# USB_OTG_AND_HOST.net
KiCad netlist of a schematic drawn in Altium Designer
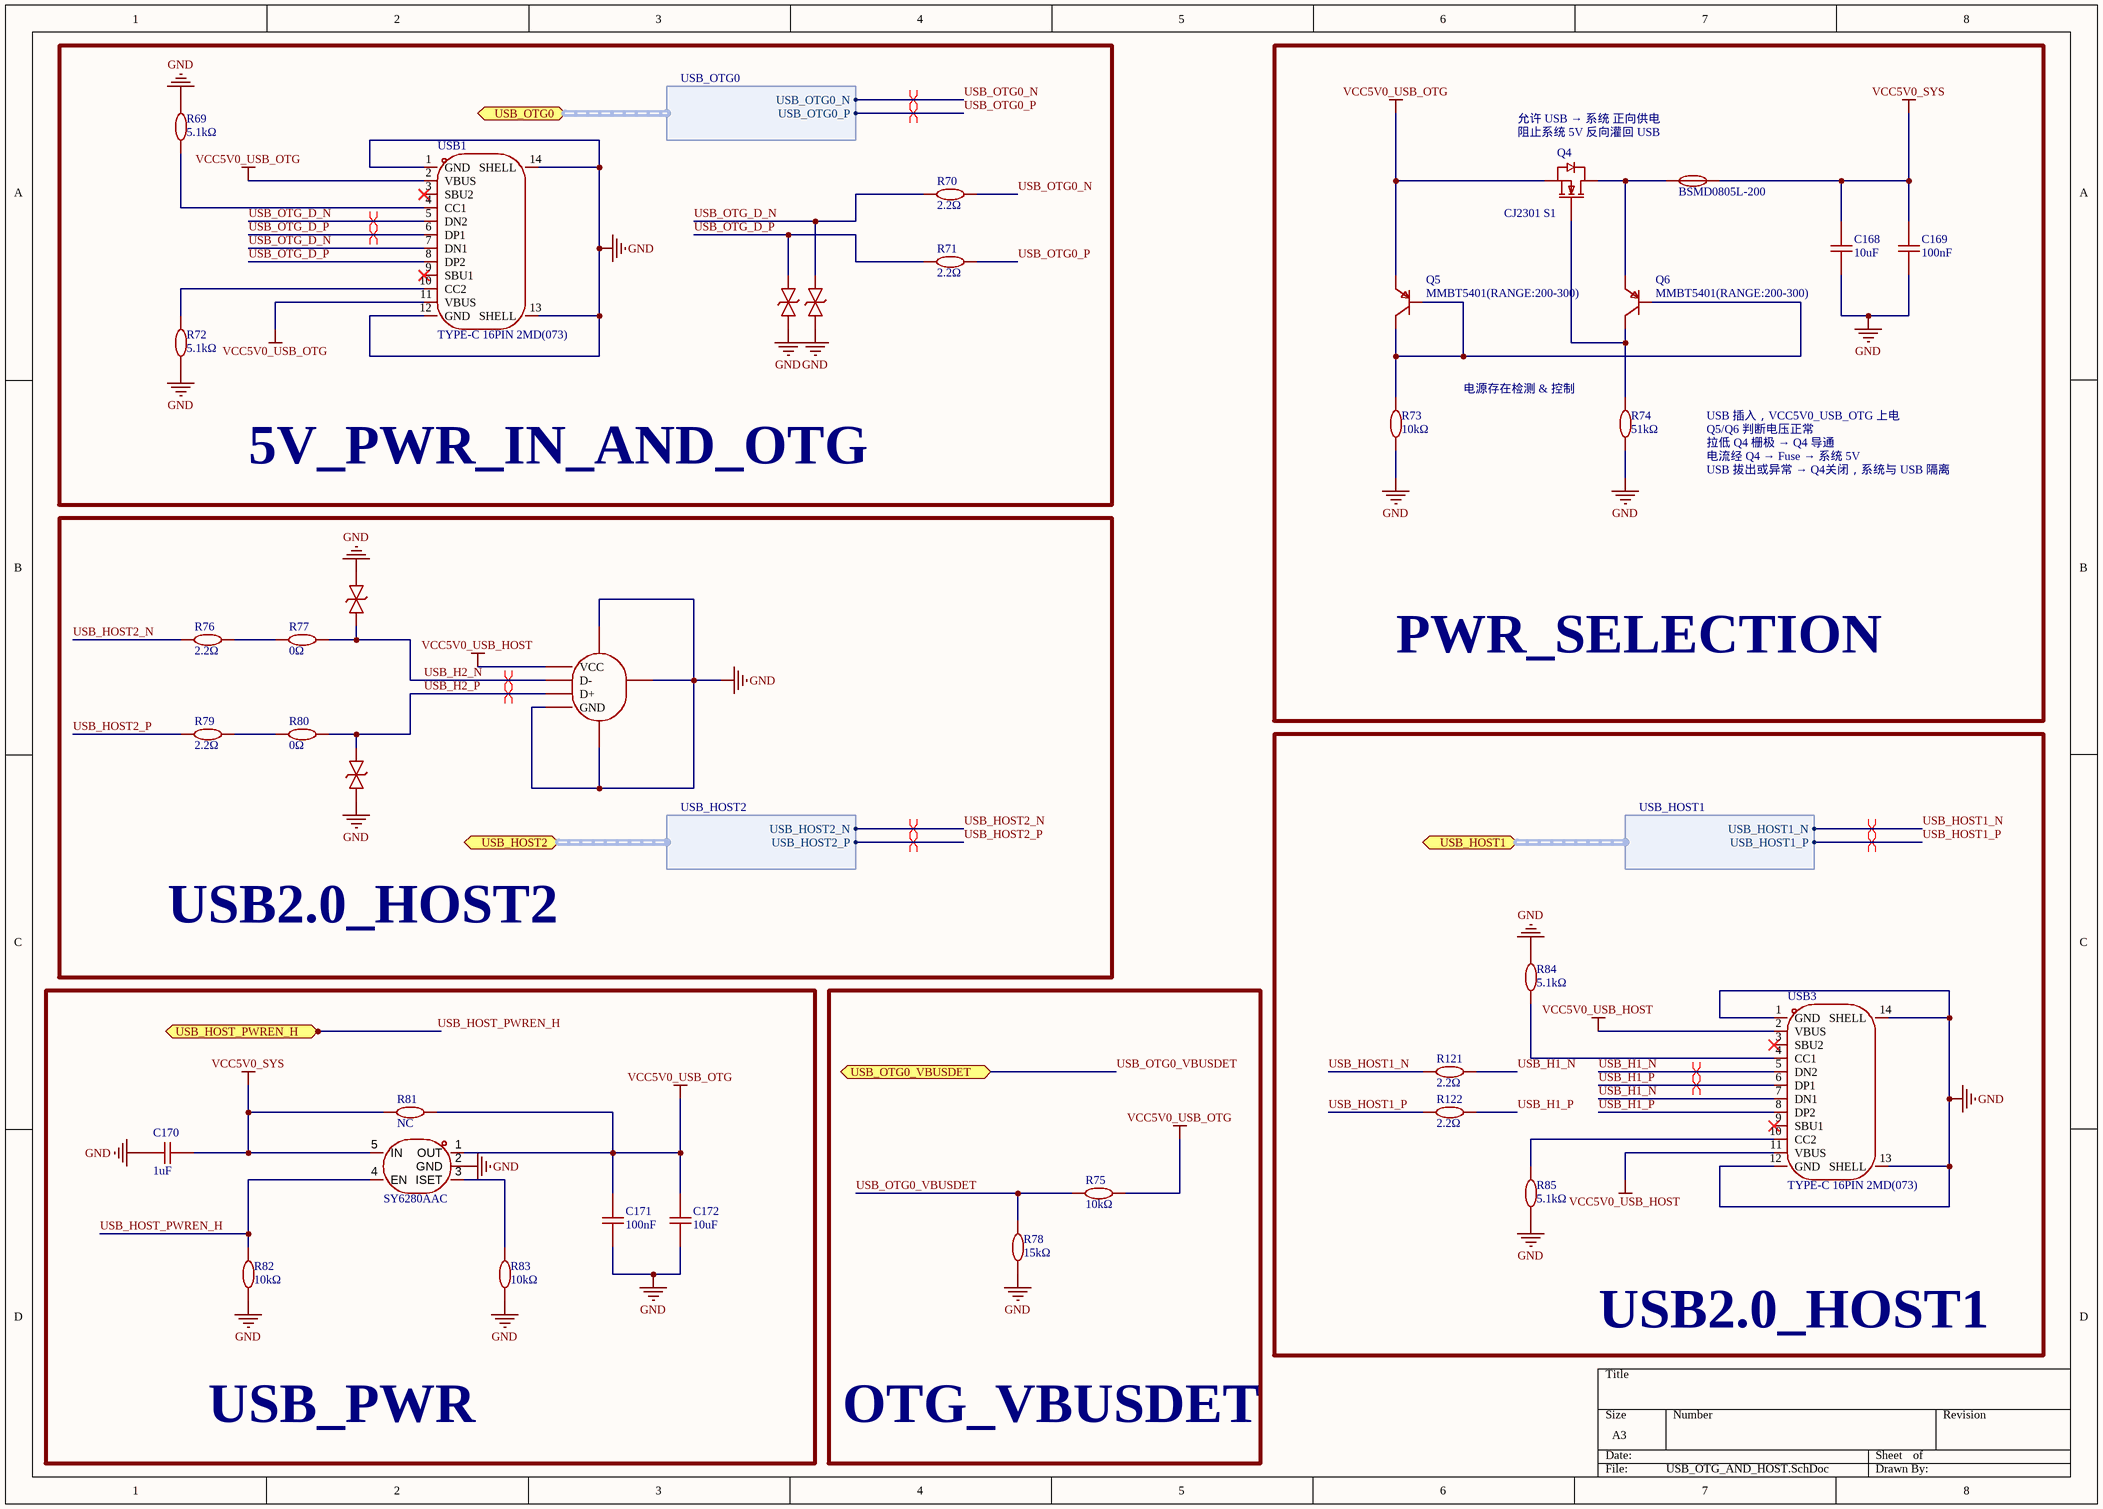
[diagram p0: USB_OTG_AND_HOST.SchDoc]

(export (version "E")
  (design (tool "Eeschema 10.0.6"))
  (components
    (comp (ref "C168")
      (value "10uF")
      (footprint "C0603")
      (description "10V 10uF X5R ±10% 0603 Ceramic Capacitors ROHS")
      (libsource (lib "RLC") (part "10uF"))
    )
    (comp (ref "C169")
      (value "100nF")
      (footprint "C0402")
      (description "50V 100nF X7R ±10% 0402 Ceramic Capacitors ROHS")
      (libsource (lib "RLC") (part "100nF"))
    )
    (comp (ref "C170")
      (value "1uF")
      (footprint "C0402")
      (description "50V 1uF X5R ±10% 0402 Ceramic Capacitors ROHS")
      (libsource (lib "RLC") (part "1uF"))
    )
    (comp (ref "C171")
      (value "100nF")
      (footprint "C0402")
      (description "50V 100nF X7R ±10% 0402 Ceramic Capacitors ROHS")
      (libsource (lib "RLC") (part "100nF"))
    )
    (comp (ref "C172")
      (value "10uF")
      (footprint "C0603")
      (description "10V 10uF X5R ±10% 0603 Ceramic Capacitors ROHS")
      (libsource (lib "RLC") (part "10uF"))
    )
    (comp (ref "F1")
      (value "BSMD0805L-200")
      (footprint "F0805")
      (description "6V 2A 0805自恢复")
      (libsource (lib "LED") (part "BSMD0805L-200"))
    )
    (comp (ref "Q4")
      (value "CJ2301 S1")
      (footprint "SOT-23_L2.9-W1.3-P1.90-LS2.4-BR")
      (description "1个P沟道 耐压:20V 电流:2.3A ,-20V,-2.3A,112mΩ@-4.5V")
      (libsource (lib "Transistor") (part "CJ2301 S1"))
    )
    (comp (ref "Q5")
      (value "MMBT5401(RANGE:200-300)")
      (footprint "SOT-23_L2.9-W1.3-P1.90-LS2.4-BR")
      (description "PNP hfe=200~300 PNP 电流:0.6A 电压:150V")
      (libsource (lib "Transistor") (part "MMBT5401(RANGE{colon}200-300)"))
    )
    (comp (ref "Q6")
      (value "MMBT5401(RANGE:200-300)")
      (footprint "SOT-23_L2.9-W1.3-P1.90-LS2.4-BR")
      (description "PNP hfe=200~300 PNP 电流:0.6A 电压:150V")
      (libsource (lib "Transistor") (part "MMBT5401(RANGE{colon}200-300)"))
    )
    (comp (ref "R69")
      (value "5.1kΩ")
      (footprint "R0402")
      (description "5.1kΩ 62.5mW 50V ±100ppm/℃ Thick Film Resistor ±1% 0402 Chip Resistor - Surface Mount ROHS")
      (libsource (lib "RLC") (part "5.1kΩ"))
    )
    (comp (ref "R70")
      (value "2.2Ω")
      (footprint "R0402")
      (description "小尺寸、重量轻。降低组装成本,与贴片机匹配。适用于波峰焊和回流焊")
      (libsource (lib "RLC") (part "2.2Ω"))
    )
    (comp (ref "R71")
      (value "2.2Ω")
      (footprint "R0402")
      (description "小尺寸、重量轻。降低组装成本,与贴片机匹配。适用于波峰焊和回流焊")
      (libsource (lib "RLC") (part "2.2Ω"))
    )
    (comp (ref "R72")
      (value "5.1kΩ")
      (footprint "R0402")
      (description "5.1kΩ 62.5mW 50V ±100ppm/℃ Thick Film Resistor ±1% 0402 Chip Resistor - Surface Mount ROHS")
      (libsource (lib "RLC") (part "5.1kΩ"))
    )
    (comp (ref "R73")
      (value "10kΩ")
      (footprint "R0402")
      (description "62.5mW 10kΩ 50V ±100ppm/℃ Thick Film Resistor ±1% 0402 Chip Resistor - Surface Mount ROHS")
      (libsource (lib "RLC") (part "10kΩ"))
    )
    (comp (ref "R74")
      (value "51kΩ")
      (footprint "R0402")
      (description "51kΩ 62.5mW 50V ±100ppm/℃ Thick Film Resistor ±1% 0402 Chip Resistor - Surface Mount ROHS")
      (libsource (lib "RLC") (part "51kΩ"))
    )
    (comp (ref "R75")
      (value "10kΩ")
      (footprint "R0402")
      (description "62.5mW 10kΩ 50V ±100ppm/℃ Thick Film Resistor ±1% 0402 Chip Resistor - Surface Mount ROHS")
      (libsource (lib "RLC") (part "10kΩ"))
    )
    (comp (ref "R76")
      (value "2.2Ω")
      (footprint "R0402")
      (description "小尺寸、重量轻。降低组装成本,与贴片机匹配。适用于波峰焊和回流焊")
      (libsource (lib "RLC") (part "2.2Ω"))
    )
    (comp (ref "R77")
      (value "0Ω")
      (footprint "R0402")
      (description "0Ω 62.5mW 50V Thick Film Resistor ±1% 0402 Chip Resistor - Surface Mount ROHS")
      (libsource (lib "RLC") (part "0Ω"))
    )
    (comp (ref "R78")
      (value "15kΩ")
      (footprint "R0402")
      (description "62.5mW 15kΩ 50V ±100ppm/℃ Thick Film Resistor ±1% 0402 Chip Resistor - Surface Mount ROHS")
      (libsource (lib "RLC") (part "15kΩ"))
    )
    (comp (ref "R79")
      (value "2.2Ω")
      (footprint "R0402")
      (description "小尺寸、重量轻。降低组装成本,与贴片机匹配。适用于波峰焊和回流焊")
      (libsource (lib "RLC") (part "2.2Ω"))
    )
    (comp (ref "R80")
      (value "0Ω")
      (footprint "R0402")
      (description "0Ω 62.5mW 50V Thick Film Resistor ±1% 0402 Chip Resistor - Surface Mount ROHS")
      (libsource (lib "RLC") (part "0Ω"))
    )
    (comp (ref "R81")
      (value "NC")
      (footprint "R0402")
      (description "10Ω 62.5mW 50V ±200ppm/℃ Thick Film Resistor ±1% 0402 Chip Resistor - Surface Mount ROHS")
      (libsource (lib "RLC") (part "10Ω"))
    )
    (comp (ref "R82")
      (value "10kΩ")
      (footprint "R0402")
      (description "62.5mW 10kΩ 50V ±100ppm/℃ Thick Film Resistor ±1% 0402 Chip Resistor - Surface Mount ROHS")
      (libsource (lib "RLC") (part "10kΩ"))
    )
    (comp (ref "R83")
      (value "10kΩ")
      (footprint "R0402")
      (description "62.5mW 10kΩ 50V ±100ppm/℃ Thick Film Resistor ±1% 0402 Chip Resistor - Surface Mount ROHS")
      (libsource (lib "RLC") (part "10kΩ"))
    )
    (comp (ref "R84")
      (value "5.1kΩ")
      (footprint "R0402")
      (description "5.1kΩ 62.5mW 50V ±100ppm/℃ Thick Film Resistor ±1% 0402 Chip Resistor - Surface Mount ROHS")
      (libsource (lib "RLC") (part "5.1kΩ"))
    )
    (comp (ref "R85")
      (value "5.1kΩ")
      (footprint "R0402")
      (description "5.1kΩ 62.5mW 50V ±100ppm/℃ Thick Film Resistor ±1% 0402 Chip Resistor - Surface Mount ROHS")
      (libsource (lib "RLC") (part "5.1kΩ"))
    )
    (comp (ref "R121")
      (value "2.2Ω")
      (footprint "R0402")
      (description "小尺寸、重量轻。降低组装成本,与贴片机匹配。适用于波峰焊和回流焊")
      (libsource (lib "RLC") (part "2.2Ω"))
    )
    (comp (ref "R122")
      (value "2.2Ω")
      (footprint "R0402")
      (description "小尺寸、重量轻。降低组装成本,与贴片机匹配。适用于波峰焊和回流焊")
      (libsource (lib "RLC") (part "2.2Ω"))
    )
    (comp (ref "U29")
      (value "ESD5451N")
      (footprint "DFN1006-2L-BI")
      (description "9A 9.8V 8V Bidirectional 5V DFN1006-2L TVS Diodes ROHS")
      (fields (field (name "MANUFACTURER") "HXY MOSFET(华轩阳电子)"))
      (libsource (lib "LED") (part "ESD5451N_C5261080"))
    )
    (comp (ref "U30")
      (value "ESD5451N")
      (footprint "DFN1006-2L-BI")
      (description "9A 9.8V 8V Bidirectional 5V DFN1006-2L TVS Diodes ROHS")
      (fields (field (name "MANUFACTURER") "HXY MOSFET(华轩阳电子)"))
      (libsource (lib "LED") (part "ESD5451N_C5261080"))
    )
    (comp (ref "U31")
      (value "ESD5451N")
      (footprint "DFN1006-2L-BI")
      (description "9A 9.8V 8V Bidirectional 5V DFN1006-2L TVS Diodes ROHS")
      (fields (field (name "MANUFACTURER") "HXY MOSFET(华轩阳电子)"))
      (libsource (lib "LED") (part "ESD5451N_C5261080"))
    )
    (comp (ref "U32")
      (value "ESD5451N")
      (footprint "DFN1006-2L-BI")
      (description "9A 9.8V 8V Bidirectional 5V DFN1006-2L TVS Diodes ROHS")
      (fields (field (name "MANUFACTURER") "HXY MOSFET(华轩阳电子)"))
      (libsource (lib "LED") (part "ESD5451N_C5261080"))
    )
    (comp (ref "U33")
      (value "SY6280AAC")
      (footprint "SOT-23-5_L3.0-W1.7-P0.95-LS2.8-BL")
      (description "低损耗功率分配开关")
      (libsource (lib "IC") (part "SY6280AAC"))
    )
    (comp (ref "USB1")
      (value "TYPE-C 16PIN 2MD(073)")
      (footprint "USB-C-SMD_TYPE-C-6PIN-2MD-073")
      (description "16pin type-c")
      (libsource (lib "Connector") (part "TYPE-C 16PIN 2MD(073)"))
    )
    (comp (ref "USB2")
      (value "AF 10.0 HC6.3")
      (footprint "USB-A-TH_AF-10.0-HC6.3")
      (description "Type-A 母 弯插")
      (fields (field (name "MANUFACTURER") "精拓金") (field (name "MANUFACTURER PART") "906-162A1011D10200"))
      (libsource (lib "Connector") (part "AF 10.0 HC6.3"))
    )
    (comp (ref "USB3")
      (value "TYPE-C 16PIN 2MD(073)")
      (footprint "USB-C-SMD_TYPE-C-6PIN-2MD-073")
      (description "16pin type-c")
      (libsource (lib "Connector") (part "TYPE-C 16PIN 2MD(073)"))
    )
  )
  (nets
    (net (code "4") (name "/USB_H1_N") (class "Default")
      (node (ref "R121") (pin "2") (pinfunction "2_2") (pintype "passive"))
      (node (ref "USB3") (pin "5") (pinfunction "DN2_5") (pintype "passive"))
      (node (ref "USB3") (pin "7") (pinfunction "DN1_7") (pintype "passive"))
    )
    (net (code "5") (name "/USB_H1_P") (class "Default")
      (node (ref "R122") (pin "2") (pinfunction "2_2") (pintype "passive"))
      (node (ref "USB3") (pin "6") (pinfunction "DP1_6") (pintype "passive"))
      (node (ref "USB3") (pin "8") (pinfunction "DP2_8") (pintype "passive"))
    )
    (net (code "6") (name "/USB_H2_N") (class "Default")
      (node (ref "R77") (pin "2") (pinfunction "2_2") (pintype "passive"))
      (node (ref "U31") (pin "1") (pinfunction "1_1") (pintype "passive"))
      (node (ref "USB2") (pin "2") (pinfunction "D-_2") (pintype "passive"))
    )
    (net (code "7") (name "/USB_H2_P") (class "Default")
      (node (ref "R80") (pin "2") (pinfunction "2_2") (pintype "passive"))
      (node (ref "U32") (pin "2") (pinfunction "2_2") (pintype "passive"))
      (node (ref "USB2") (pin "3") (pinfunction "D+_3") (pintype "passive"))
    )
    (net (code "8") (name "/USB_HOST1_N") (class "Default")
      (node (ref "R121") (pin "1") (pinfunction "1_1") (pintype "passive"))
    )
    (net (code "9") (name "/USB_HOST1_P") (class "Default")
      (node (ref "R122") (pin "1") (pinfunction "1_1") (pintype "passive"))
    )
    (net (code "10") (name "/USB_HOST2_N") (class "Default")
      (node (ref "R76") (pin "1") (pinfunction "1_1") (pintype "passive"))
    )
    (net (code "11") (name "/USB_HOST2_P") (class "Default")
      (node (ref "R79") (pin "1") (pinfunction "1_1") (pintype "passive"))
    )
    (net (code "12") (name "/USB_HOST_PWREN_H") (class "Default")
      (node (ref "R82") (pin "2") (pinfunction "2_2") (pintype "passive"))
      (node (ref "U33") (pin "4") (pinfunction "EN_4") (pintype "passive"))
    )
    (net (code "13") (name "/USB_OTG0_N") (class "Default")
      (node (ref "R70") (pin "2") (pinfunction "2_2") (pintype "passive"))
    )
    (net (code "14") (name "/USB_OTG0_P") (class "Default")
      (node (ref "R71") (pin "2") (pinfunction "2_2") (pintype "passive"))
    )
    (net (code "15") (name "/USB_OTG0_VBUSDET") (class "Default")
      (node (ref "R75") (pin "1") (pinfunction "1_1") (pintype "passive"))
      (node (ref "R78") (pin "2") (pinfunction "2_2") (pintype "passive"))
    )
    (net (code "16") (name "/USB_OTG_D_N") (class "Default")
      (node (ref "R70") (pin "1") (pinfunction "1_1") (pintype "passive"))
      (node (ref "U30") (pin "2") (pinfunction "2_2") (pintype "passive"))
      (node (ref "USB1") (pin "5") (pinfunction "DN2_5") (pintype "passive"))
      (node (ref "USB1") (pin "7") (pinfunction "DN1_7") (pintype "passive"))
    )
    (net (code "17") (name "/USB_OTG_D_P") (class "Default")
      (node (ref "R71") (pin "1") (pinfunction "1_1") (pintype "passive"))
      (node (ref "U29") (pin "2") (pinfunction "2_2") (pintype "passive"))
      (node (ref "USB1") (pin "6") (pinfunction "DP1_6") (pintype "passive"))
      (node (ref "USB1") (pin "8") (pinfunction "DP2_8") (pintype "passive"))
    )
    (net (code "21") (name "GND") (class "Default")
      (node (ref "C168") (pin "1") (pinfunction "1_1") (pintype "passive"))
      (node (ref "C169") (pin "1") (pinfunction "1_1") (pintype "passive"))
      (node (ref "C170") (pin "1") (pinfunction "1_1") (pintype "passive"))
      (node (ref "C171") (pin "1") (pinfunction "1_1") (pintype "passive"))
      (node (ref "C172") (pin "1") (pinfunction "1_1") (pintype "passive"))
      (node (ref "R69") (pin "2") (pinfunction "2_2") (pintype "passive"))
      (node (ref "R72") (pin "1") (pinfunction "1_1") (pintype "passive"))
      (node (ref "R73") (pin "1") (pinfunction "1_1") (pintype "passive"))
      (node (ref "R74") (pin "1") (pinfunction "1_1") (pintype "passive"))
      (node (ref "R78") (pin "1") (pinfunction "1_1") (pintype "passive"))
      (node (ref "R82") (pin "1") (pinfunction "1_1") (pintype "passive"))
      (node (ref "R83") (pin "1") (pinfunction "1_1") (pintype "passive"))
      (node (ref "R84") (pin "2") (pinfunction "2_2") (pintype "passive"))
      (node (ref "R85") (pin "1") (pinfunction "1_1") (pintype "passive"))
      (node (ref "U29") (pin "1") (pinfunction "1_1") (pintype "passive"))
      (node (ref "U30") (pin "1") (pinfunction "1_1") (pintype "passive"))
      (node (ref "U31") (pin "2") (pinfunction "2_2") (pintype "passive"))
      (node (ref "U32") (pin "1") (pinfunction "1_1") (pintype "passive"))
      (node (ref "U33") (pin "2") (pinfunction "GND_2") (pintype "passive"))
      (node (ref "USB1") (pin "1") (pinfunction "GND_1") (pintype "passive"))
      (node (ref "USB1") (pin "12") (pinfunction "GND_12") (pintype "passive"))
      (node (ref "USB1") (pin "13") (pinfunction "SHELL_13") (pintype "passive"))
      (node (ref "USB1") (pin "14") (pinfunction "SHELL_14") (pintype "passive"))
      (node (ref "USB2") (pin "4") (pinfunction "GND_4") (pintype "passive"))
      (node (ref "USB2") (pin "5") (pinfunction "5_5") (pintype "passive"))
      (node (ref "USB2") (pin "6") (pinfunction "6_6") (pintype "passive"))
      (node (ref "USB2") (pin "7") (pinfunction "7_7") (pintype "passive"))
      (node (ref "USB3") (pin "1") (pinfunction "GND_1") (pintype "passive"))
      (node (ref "USB3") (pin "12") (pinfunction "GND_12") (pintype "passive"))
      (node (ref "USB3") (pin "13") (pinfunction "SHELL_13") (pintype "passive"))
      (node (ref "USB3") (pin "14") (pinfunction "SHELL_14") (pintype "passive"))
    )
    (net (code "22") (name "Net-(Q4-D)") (class "Default")
      (node (ref "F1") (pin "1") (pinfunction "1_1") (pintype "passive"))
      (node (ref "Q4") (pin "3") (pinfunction "D_3") (pintype "passive"))
      (node (ref "Q6") (pin "2") (pinfunction "E_2") (pintype "passive"))
    )
    (net (code "23") (name "Net-(Q4-G)") (class "Default")
      (node (ref "Q4") (pin "1") (pinfunction "G_1") (pintype "passive"))
      (node (ref "Q6") (pin "3") (pinfunction "B_3") (pintype "passive"))
      (node (ref "R74") (pin "2") (pinfunction "2_2") (pintype "passive"))
    )
    (net (code "24") (name "Net-(Q5-B-Pad1)") (class "Default")
      (node (ref "Q5") (pin "1") (pinfunction "B_1") (pintype "passive"))
      (node (ref "Q5") (pin "3") (pinfunction "B_3") (pintype "passive"))
      (node (ref "Q6") (pin "1") (pinfunction "B_1") (pintype "passive"))
      (node (ref "R73") (pin "2") (pinfunction "2_2") (pintype "passive"))
    )
    (net (code "25") (name "Net-(R76-Pad2)") (class "Default")
      (node (ref "R76") (pin "2") (pinfunction "2_2") (pintype "passive"))
      (node (ref "R77") (pin "1") (pinfunction "1_1") (pintype "passive"))
    )
    (net (code "26") (name "Net-(R79-Pad2)") (class "Default")
      (node (ref "R79") (pin "2") (pinfunction "2_2") (pintype "passive"))
      (node (ref "R80") (pin "1") (pinfunction "1_1") (pintype "passive"))
    )
    (net (code "27") (name "Net-(U33-ISET)") (class "Default")
      (node (ref "R83") (pin "2") (pinfunction "2_2") (pintype "passive"))
      (node (ref "U33") (pin "3") (pinfunction "ISET_3") (pintype "passive"))
    )
    (net (code "28") (name "Net-(USB1-CC1)") (class "Default")
      (node (ref "R69") (pin "1") (pinfunction "1_1") (pintype "passive"))
      (node (ref "USB1") (pin "4") (pinfunction "CC1_4") (pintype "passive"))
    )
    (net (code "29") (name "Net-(USB1-CC2)") (class "Default")
      (node (ref "R72") (pin "2") (pinfunction "2_2") (pintype "passive"))
      (node (ref "USB1") (pin "10") (pinfunction "CC2_10") (pintype "passive"))
    )
    (net (code "30") (name "Net-(USB3-CC1)") (class "Default")
      (node (ref "R84") (pin "1") (pinfunction "1_1") (pintype "passive"))
      (node (ref "USB3") (pin "4") (pinfunction "CC1_4") (pintype "passive"))
    )
    (net (code "31") (name "Net-(USB3-CC2)") (class "Default")
      (node (ref "R85") (pin "2") (pinfunction "2_2") (pintype "passive"))
      (node (ref "USB3") (pin "10") (pinfunction "CC2_10") (pintype "passive"))
    )
    (net (code "32") (name "VCC5V0_SYS") (class "Default")
      (node (ref "C168") (pin "2") (pinfunction "2_2") (pintype "passive"))
      (node (ref "C169") (pin "2") (pinfunction "2_2") (pintype "passive"))
      (node (ref "C170") (pin "2") (pinfunction "2_2") (pintype "passive"))
      (node (ref "F1") (pin "2") (pinfunction "2_2") (pintype "passive"))
      (node (ref "R81") (pin "1") (pinfunction "1_1") (pintype "passive"))
      (node (ref "U33") (pin "5") (pinfunction "IN_5") (pintype "passive"))
    )
    (net (code "33") (name "VCC5V0_USB_HOST") (class "Default")
      (node (ref "USB2") (pin "1") (pinfunction "VCC_1") (pintype "passive"))
      (node (ref "USB3") (pin "11") (pinfunction "VBUS_11") (pintype "passive"))
      (node (ref "USB3") (pin "2") (pinfunction "VBUS_2") (pintype "passive"))
    )
    (net (code "34") (name "VCC5V0_USB_OTG") (class "Default")
      (node (ref "C171") (pin "2") (pinfunction "2_2") (pintype "passive"))
      (node (ref "C172") (pin "2") (pinfunction "2_2") (pintype "passive"))
      (node (ref "Q4") (pin "2") (pinfunction "S_2") (pintype "passive"))
      (node (ref "Q5") (pin "2") (pinfunction "E_2") (pintype "passive"))
      (node (ref "R75") (pin "2") (pinfunction "2_2") (pintype "passive"))
      (node (ref "R81") (pin "2") (pinfunction "2_2") (pintype "passive"))
      (node (ref "U33") (pin "1") (pinfunction "OUT_1") (pintype "passive"))
      (node (ref "USB1") (pin "11") (pinfunction "VBUS_11") (pintype "passive"))
      (node (ref "USB1") (pin "2") (pinfunction "VBUS_2") (pintype "passive"))
    )
    (net (code "35") (name "unconnected-(USB1-SBU1-Pad9)") (class "Default")
      (node (ref "USB1") (pin "9") (pinfunction "SBU1_9") (pintype "passive+no_connect"))
    )
    (net (code "36") (name "unconnected-(USB1-SBU2-Pad3)") (class "Default")
      (node (ref "USB1") (pin "3") (pinfunction "SBU2_3") (pintype "passive+no_connect"))
    )
    (net (code "37") (name "unconnected-(USB3-SBU1-Pad9)") (class "Default")
      (node (ref "USB3") (pin "9") (pinfunction "SBU1_9") (pintype "passive+no_connect"))
    )
    (net (code "38") (name "unconnected-(USB3-SBU2-Pad3)") (class "Default")
      (node (ref "USB3") (pin "3") (pinfunction "SBU2_3") (pintype "passive+no_connect"))
    )
  )
)
